# cnc-opto-board.net
KiCad netlist of a schematic drawn in EAGLE
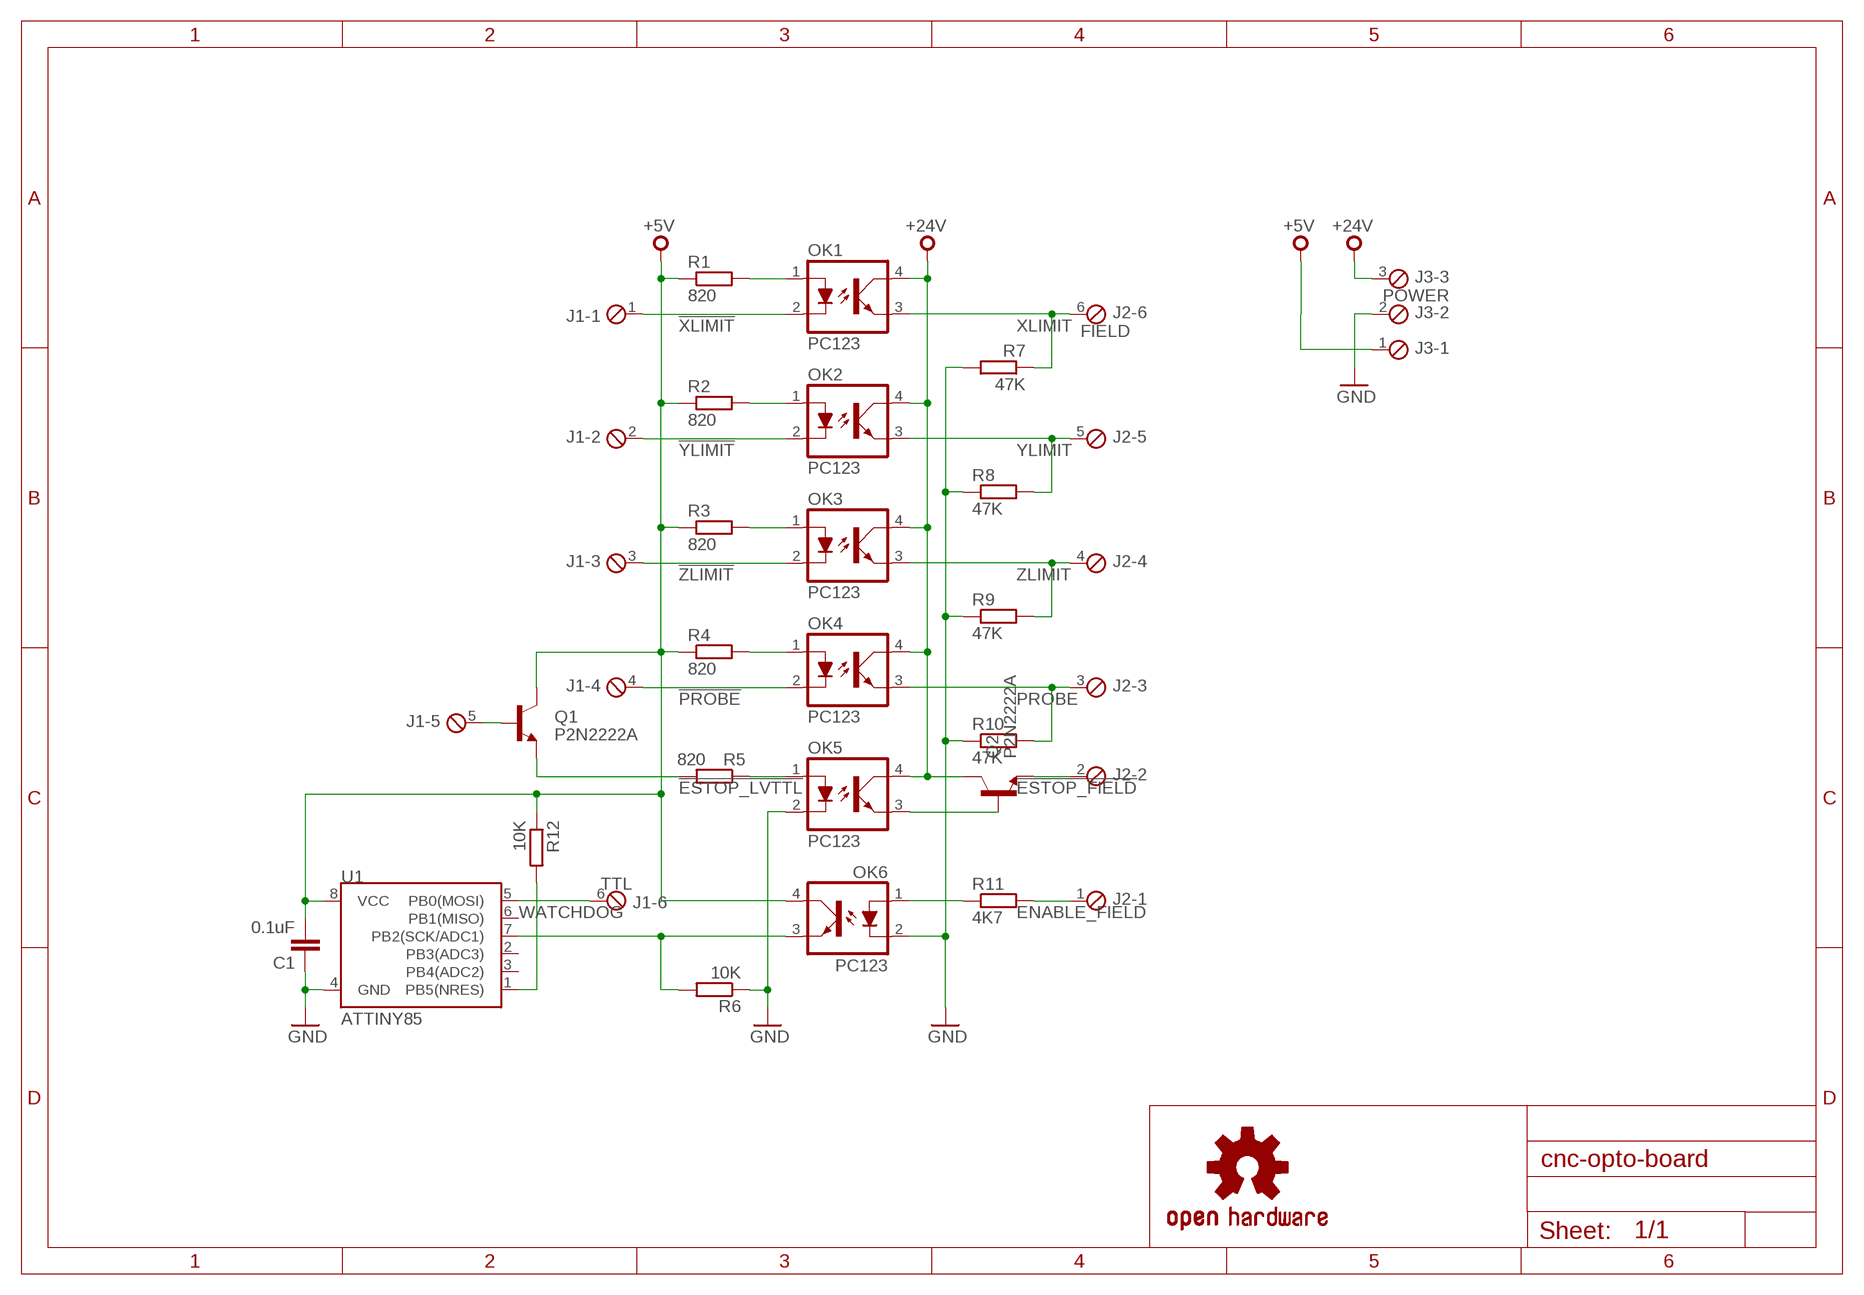
[diagram p0: schematic, sheet 1]

(export (version "E")
  (design (tool "Eeschema 10.0.6"))
  (components
    (comp (ref "C1")
      (value "0.1uF")
      (footprint "eagle-import:C050-025X075")
      (libsource (lib "eagle-import") (part "C-EU050-025X075"))
    )
    (comp (ref "J1")
      (value "TTL")
      (footprint "eagle-import:MKDS06")
      (libsource (lib "eagle-import") (part "MKDS06"))
    )
    (comp (ref "J2")
      (value "FIELD")
      (footprint "eagle-import:MKDS06")
      (libsource (lib "eagle-import") (part "MKDS06"))
    )
    (comp (ref "J3")
      (value "POWER")
      (footprint "eagle-import:MKDS03")
      (libsource (lib "eagle-import") (part "MKDS03"))
    )
    (comp (ref "LOGO1")
      (value "OSHW-LOGOL")
      (footprint "eagle-import:OSHW-LOGO-L")
      (libsource (lib "eagle-import") (part "OSHW-LOGOL"))
    )
    (comp (ref "OK1")
      (value "PC123")
      (footprint "eagle-import:DIL04")
      (libsource (lib "eagle-import") (part "PC817"))
    )
    (comp (ref "OK2")
      (value "PC123")
      (footprint "eagle-import:DIL04")
      (libsource (lib "eagle-import") (part "PC817"))
    )
    (comp (ref "OK3")
      (value "PC123")
      (footprint "eagle-import:DIL04")
      (libsource (lib "eagle-import") (part "PC817"))
    )
    (comp (ref "OK4")
      (value "PC123")
      (footprint "eagle-import:DIL04")
      (libsource (lib "eagle-import") (part "PC817"))
    )
    (comp (ref "OK5")
      (value "PC123")
      (footprint "eagle-import:DIL04")
      (libsource (lib "eagle-import") (part "PC817"))
    )
    (comp (ref "OK6")
      (value "PC123")
      (footprint "eagle-import:DIL04")
      (libsource (lib "eagle-import") (part "PC817"))
    )
    (comp (ref "Q1")
      (value "P2N2222A")
      (footprint "eagle-import:TO-92")
      (libsource (lib "eagle-import") (part "TRANSISTOR_NPN_2PTH"))
    )
    (comp (ref "Q2")
      (value "P2N2222A")
      (footprint "eagle-import:TO-92")
      (libsource (lib "eagle-import") (part "TRANSISTOR_NPN_2PTH"))
    )
    (comp (ref "R1")
      (value "820")
      (footprint "eagle-import:0207_10")
      (libsource (lib "eagle-import") (part "R-EU_0207/10"))
    )
    (comp (ref "R2")
      (value "820")
      (footprint "eagle-import:0207_10")
      (libsource (lib "eagle-import") (part "R-EU_0207/10"))
    )
    (comp (ref "R3")
      (value "820")
      (footprint "eagle-import:0207_10")
      (libsource (lib "eagle-import") (part "R-EU_0207/10"))
    )
    (comp (ref "R4")
      (value "820")
      (footprint "eagle-import:0207_10")
      (libsource (lib "eagle-import") (part "R-EU_0207/10"))
    )
    (comp (ref "R5")
      (value "820")
      (footprint "eagle-import:0207_10")
      (libsource (lib "eagle-import") (part "R-EU_0207/10"))
    )
    (comp (ref "R6")
      (value "10K")
      (footprint "eagle-import:0207_10")
      (libsource (lib "eagle-import") (part "R-EU_0207/10"))
    )
    (comp (ref "R7")
      (value "47K")
      (footprint "eagle-import:0207_10")
      (libsource (lib "eagle-import") (part "R-EU_0207/10"))
    )
    (comp (ref "R8")
      (value "47K")
      (footprint "eagle-import:0207_10")
      (libsource (lib "eagle-import") (part "R-EU_0207/10"))
    )
    (comp (ref "R9")
      (value "47K")
      (footprint "eagle-import:0207_10")
      (libsource (lib "eagle-import") (part "R-EU_0207/10"))
    )
    (comp (ref "R10")
      (value "47K")
      (footprint "eagle-import:0207_10")
      (libsource (lib "eagle-import") (part "R-EU_0207/10"))
    )
    (comp (ref "R11")
      (value "4K7")
      (footprint "eagle-import:0207_10")
      (libsource (lib "eagle-import") (part "R-EU_0207/10"))
    )
    (comp (ref "R12")
      (value "10K")
      (footprint "eagle-import:0207_10")
      (libsource (lib "eagle-import") (part "R-EU_0207/10"))
    )
    (comp (ref "U1")
      (value "ATTINY85")
      (footprint "eagle-import:DIL08")
      (libsource (lib "eagle-import") (part "ATTINY45DIP8L"))
    )
  )
  (nets
    (net (code "1") (name "+5V") (class "Default")
      (node (ref "C1") (pin "2") (pinfunction "2_2") (pintype "passive"))
      (node (ref "J3") (pin "1") (pinfunction "1_1") (pintype "passive"))
      (node (ref "OK6") (pin "4") (pinfunction "COL_4") (pintype "passive"))
      (node (ref "Q1") (pin "1") (pinfunction "C_1") (pintype "passive"))
      (node (ref "R1") (pin "1") (pinfunction "1_1") (pintype "passive"))
      (node (ref "R12") (pin "1") (pinfunction "1_1") (pintype "passive"))
      (node (ref "R2") (pin "1") (pinfunction "1_1") (pintype "passive"))
      (node (ref "R3") (pin "1") (pinfunction "1_1") (pintype "passive"))
      (node (ref "R4") (pin "1") (pinfunction "1_1") (pintype "passive"))
      (node (ref "U1") (pin "8") (pinfunction "VCC_8") (pintype "bidirectional"))
    )
    (net (code "2") (name "+24V") (class "Default")
      (node (ref "J3") (pin "3") (pinfunction "1_3") (pintype "passive"))
      (node (ref "OK1") (pin "4") (pinfunction "COL_4") (pintype "passive"))
      (node (ref "OK2") (pin "4") (pinfunction "COL_4") (pintype "passive"))
      (node (ref "OK3") (pin "4") (pinfunction "COL_4") (pintype "passive"))
      (node (ref "OK4") (pin "4") (pinfunction "COL_4") (pintype "passive"))
      (node (ref "OK5") (pin "4") (pinfunction "COL_4") (pintype "passive"))
      (node (ref "Q2") (pin "1") (pinfunction "C_1") (pintype "passive"))
    )
    (net (code "3") (name "/ENABLE_FIELD") (class "Default")
      (node (ref "J2") (pin "1") (pinfunction "1_1") (pintype "passive"))
      (node (ref "R11") (pin "2") (pinfunction "2_2") (pintype "passive"))
    )
    (net (code "4") (name "/PROBE") (class "Default")
      (node (ref "J2") (pin "3") (pinfunction "1_3") (pintype "passive"))
      (node (ref "OK4") (pin "3") (pinfunction "EMIT_3") (pintype "passive"))
      (node (ref "R10") (pin "2") (pinfunction "2_2") (pintype "passive"))
    )
    (net (code "5") (name "/WATCHDOG") (class "Default")
      (node (ref "J1") (pin "6") (pinfunction "1_6") (pintype "passive"))
      (node (ref "U1") (pin "5") (pinfunction "PB0(MOSI)_5") (pintype "bidirectional"))
    )
    (net (code "6") (name "/XLIMIT") (class "Default")
      (node (ref "J2") (pin "6") (pinfunction "1_6") (pintype "passive"))
      (node (ref "OK1") (pin "3") (pinfunction "EMIT_3") (pintype "passive"))
      (node (ref "R7") (pin "1") (pinfunction "1_1") (pintype "passive"))
    )
    (net (code "7") (name "/YLIMIT") (class "Default")
      (node (ref "J2") (pin "5") (pinfunction "1_5") (pintype "passive"))
      (node (ref "OK2") (pin "3") (pinfunction "EMIT_3") (pintype "passive"))
      (node (ref "R8") (pin "2") (pinfunction "2_2") (pintype "passive"))
    )
    (net (code "8") (name "/ZLIMIT") (class "Default")
      (node (ref "J2") (pin "4") (pinfunction "1_4") (pintype "passive"))
      (node (ref "OK3") (pin "3") (pinfunction "EMIT_3") (pintype "passive"))
      (node (ref "R9") (pin "2") (pinfunction "2_2") (pintype "passive"))
    )
    (net (code "9") (name "/~{ESTOP_FIELD}") (class "Default")
      (node (ref "J2") (pin "2") (pinfunction "1_2") (pintype "passive"))
      (node (ref "Q2") (pin "3") (pinfunction "E_3") (pintype "passive"))
    )
    (net (code "10") (name "/~{ESTOP_LVTTL}") (class "Default")
      (node (ref "OK5") (pin "1") (pinfunction "A_1") (pintype "passive"))
      (node (ref "R5") (pin "1") (pinfunction "1_1") (pintype "passive"))
    )
    (net (code "11") (name "/~{PROBE}") (class "Default")
      (node (ref "J1") (pin "4") (pinfunction "1_4") (pintype "passive"))
      (node (ref "OK4") (pin "2") (pinfunction "C_2") (pintype "passive"))
    )
    (net (code "12") (name "/~{XLIMIT}") (class "Default")
      (node (ref "J1") (pin "1") (pinfunction "1_1") (pintype "passive"))
      (node (ref "OK1") (pin "2") (pinfunction "C_2") (pintype "passive"))
    )
    (net (code "13") (name "/~{YLIMIT}") (class "Default")
      (node (ref "J1") (pin "2") (pinfunction "1_2") (pintype "passive"))
      (node (ref "OK2") (pin "2") (pinfunction "C_2") (pintype "passive"))
    )
    (net (code "14") (name "/~{ZLIMIT}") (class "Default")
      (node (ref "J1") (pin "3") (pinfunction "1_3") (pintype "passive"))
      (node (ref "OK3") (pin "2") (pinfunction "C_2") (pintype "passive"))
    )
    (net (code "15") (name "GND") (class "Default")
      (node (ref "C1") (pin "1") (pinfunction "1_1") (pintype "passive"))
      (node (ref "J3") (pin "2") (pinfunction "1_2") (pintype "passive"))
      (node (ref "OK5") (pin "2") (pinfunction "C_2") (pintype "passive"))
      (node (ref "OK6") (pin "2") (pinfunction "C_2") (pintype "passive"))
      (node (ref "R10") (pin "1") (pinfunction "1_1") (pintype "passive"))
      (node (ref "R6") (pin "1") (pinfunction "1_1") (pintype "passive"))
      (node (ref "R7") (pin "2") (pinfunction "2_2") (pintype "passive"))
      (node (ref "R8") (pin "1") (pinfunction "1_1") (pintype "passive"))
      (node (ref "R9") (pin "1") (pinfunction "1_1") (pintype "passive"))
      (node (ref "U1") (pin "4") (pinfunction "GND_4") (pintype "bidirectional"))
    )
    (net (code "16") (name "Net-(J1E-1)") (class "Default")
      (node (ref "J1") (pin "5") (pinfunction "1_5") (pintype "passive"))
      (node (ref "Q1") (pin "2") (pinfunction "B_2") (pintype "passive"))
    )
    (net (code "17") (name "Net-(OK1-A)") (class "Default")
      (node (ref "OK1") (pin "1") (pinfunction "A_1") (pintype "passive"))
      (node (ref "R1") (pin "2") (pinfunction "2_2") (pintype "passive"))
    )
    (net (code "18") (name "Net-(OK2-A)") (class "Default")
      (node (ref "OK2") (pin "1") (pinfunction "A_1") (pintype "passive"))
      (node (ref "R2") (pin "2") (pinfunction "2_2") (pintype "passive"))
    )
    (net (code "19") (name "Net-(OK3-A)") (class "Default")
      (node (ref "OK3") (pin "1") (pinfunction "A_1") (pintype "passive"))
      (node (ref "R3") (pin "2") (pinfunction "2_2") (pintype "passive"))
    )
    (net (code "20") (name "Net-(OK4-A)") (class "Default")
      (node (ref "OK4") (pin "1") (pinfunction "A_1") (pintype "passive"))
      (node (ref "R4") (pin "2") (pinfunction "2_2") (pintype "passive"))
    )
    (net (code "21") (name "Net-(OK5-EMIT)") (class "Default")
      (node (ref "OK5") (pin "3") (pinfunction "EMIT_3") (pintype "passive"))
      (node (ref "Q2") (pin "2") (pinfunction "B_2") (pintype "passive"))
    )
    (net (code "22") (name "Net-(OK6-A)") (class "Default")
      (node (ref "OK6") (pin "1") (pinfunction "A_1") (pintype "passive"))
      (node (ref "R11") (pin "1") (pinfunction "1_1") (pintype "passive"))
    )
    (net (code "23") (name "Net-(OK6-EMIT)") (class "Default")
      (node (ref "OK6") (pin "3") (pinfunction "EMIT_3") (pintype "passive"))
      (node (ref "R6") (pin "2") (pinfunction "2_2") (pintype "passive"))
      (node (ref "U1") (pin "7") (pinfunction "PB2(SCK/ADC1)_7") (pintype "bidirectional"))
    )
    (net (code "24") (name "Net-(Q1-E)") (class "Default")
      (node (ref "Q1") (pin "3") (pinfunction "E_3") (pintype "passive"))
      (node (ref "R5") (pin "2") (pinfunction "2_2") (pintype "passive"))
    )
    (net (code "25") (name "Net-(U1-PB5(NRES))") (class "Default")
      (node (ref "R12") (pin "2") (pinfunction "2_2") (pintype "passive"))
      (node (ref "U1") (pin "1") (pinfunction "PB5(NRES)_1") (pintype "bidirectional"))
    )
    (net (code "26") (name "unconnected-(U1-PB1(MISO)-Pad6)") (class "Default")
      (node (ref "U1") (pin "6") (pinfunction "PB1(MISO)_6") (pintype "bidirectional"))
    )
    (net (code "27") (name "unconnected-(U1-PB3(ADC3)-Pad2)") (class "Default")
      (node (ref "U1") (pin "2") (pinfunction "PB3(ADC3)_2") (pintype "bidirectional"))
    )
    (net (code "28") (name "unconnected-(U1-PB4(ADC2)-Pad3)") (class "Default")
      (node (ref "U1") (pin "3") (pinfunction "PB4(ADC2)_3") (pintype "bidirectional"))
    )
  )
)
